# relay_bridge.net
KiCad netlist of a schematic drawn in Altium Designer
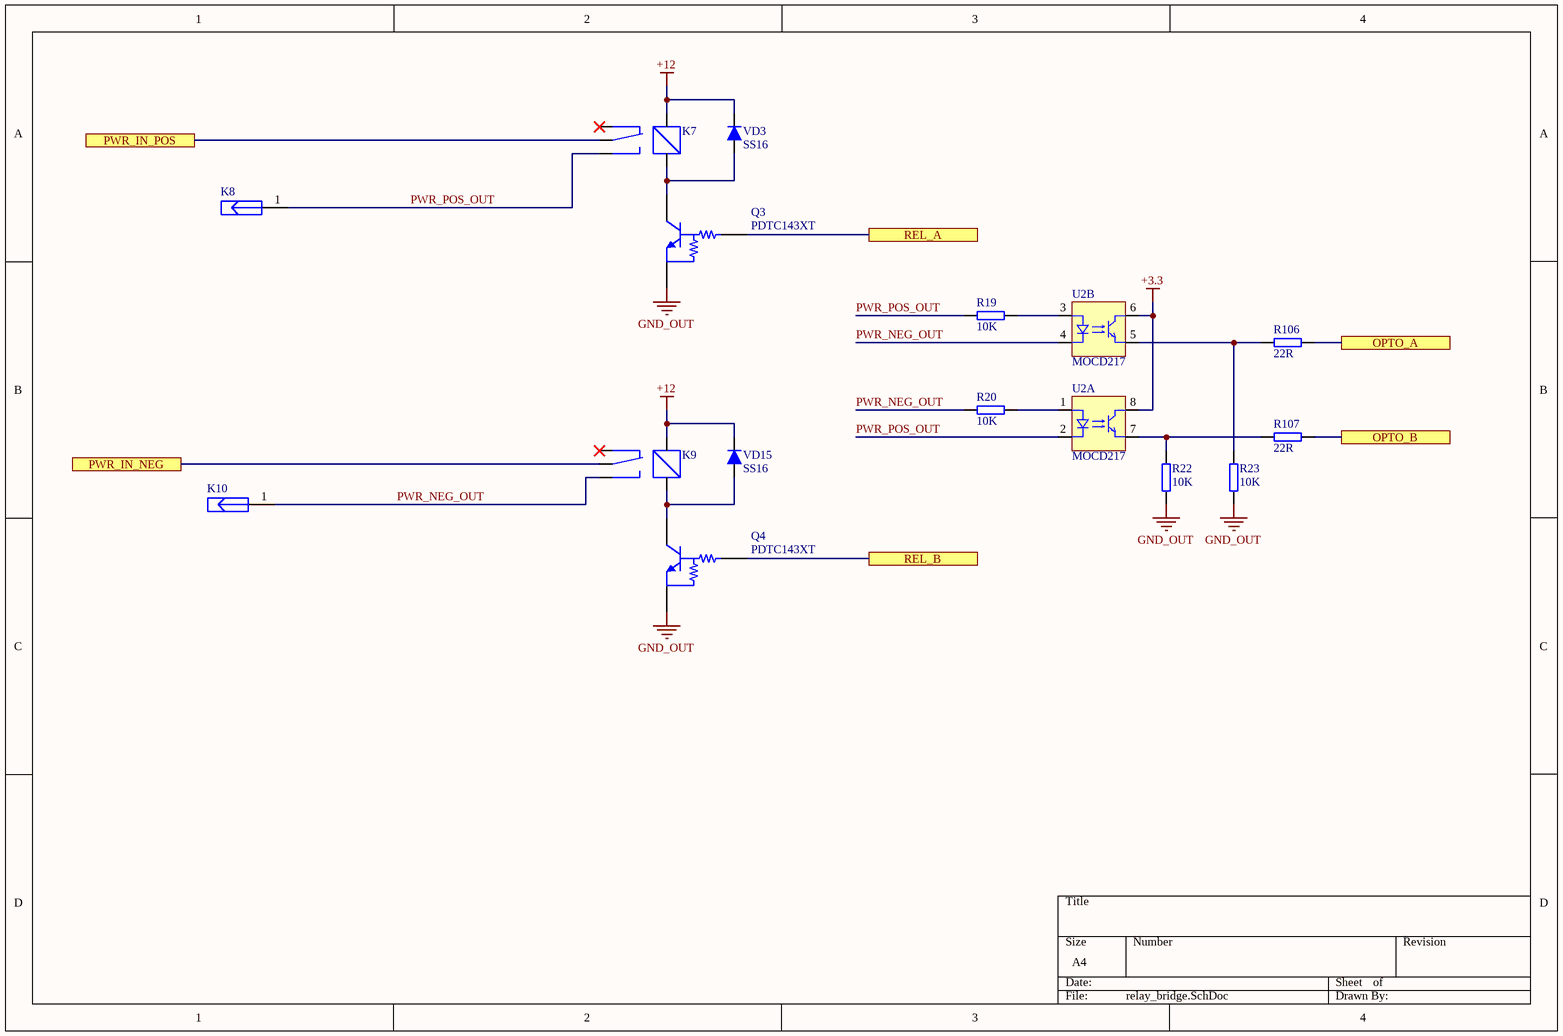
[diagram p0: relay_bridge.SchDoc]

(export (version "E")
  (design (tool "Eeschema 10.0.6"))
  (components
    (comp (ref "K7") (value "~") (footprint "REL: SRD-03VDC") (libsource (lib "OTHER") (part "Relay")))
    (comp (ref "K8") (value "~") (footprint "CON: 8191") (libsource (lib "OTHER") (part "PCB CON")))
    (comp (ref "K9") (value "~") (footprint "REL: SRD-03VDC") (libsource (lib "OTHER") (part "Relay")))
    (comp (ref "K10") (value "~") (footprint "CON: 8191") (libsource (lib "OTHER") (part "PCB CON")))
    (comp (ref "Q3")
      (value "PDTC143XT")
      (footprint "SOT23_N")
      (description "NPN Resistor-equipped Transistor")
      (fields (field (name "PUBLISHER") "Altium Limited"))
      (libsource (lib "Philips Discrete BJT - Low Power") (part "PDTC143XT"))
    )
    (comp (ref "Q4")
      (value "PDTC143XT")
      (footprint "SOT23_N")
      (description "NPN Resistor-equipped Transistor")
      (fields (field (name "PUBLISHER") "Altium Limited"))
      (libsource (lib "Philips Discrete BJT - Low Power") (part "PDTC143XT"))
    )
    (comp (ref "R19") (value "10K") (footprint "RES: 0603") (libsource (lib "PASSIVE") (part "R_SMD")))
    (comp (ref "R20") (value "10K") (footprint "RES: 0603") (libsource (lib "PASSIVE") (part "R_SMD")))
    (comp (ref "R22") (value "10K") (footprint "RES: 0603") (libsource (lib "PASSIVE") (part "R_SMD")))
    (comp (ref "R23") (value "10K") (footprint "RES: 0603") (libsource (lib "PASSIVE") (part "R_SMD")))
    (comp (ref "R106") (value "22R") (footprint "RES: 0603") (libsource (lib "PASSIVE") (part "R_SMD")))
    (comp (ref "R107") (value "22R") (footprint "RES: 0603") (libsource (lib "PASSIVE") (part "R_SMD")))
    (comp (ref "U2") (value "MOCD217") (footprint "8-SOIC") (libsource (lib "ANALOG") (part "MOCD217")))
    (comp (ref "VD3") (value "SS16") (footprint "DIODE: SMA") (libsource (lib "DIODES") (part "DIODE_SMD")))
    (comp (ref "VD15") (value "SS16") (footprint "DIODE: SMA") (libsource (lib "DIODES") (part "DIODE_SMD")))
  )
  (nets
    (net (code "1") (name "+3.3") (class "Default")
      (node (ref "U2") (pin "6") (pinfunction "C_6") (pintype "passive"))
      (node (ref "U2") (pin "8") (pinfunction "C_8") (pintype "passive"))
    )
    (net (code "2") (name "+12") (class "Default")
      (node (ref "K7") (pin "1") (pinfunction "a_1") (pintype "passive"))
      (node (ref "K9") (pin "1") (pinfunction "a_1") (pintype "passive"))
      (node (ref "VD15") (pin "2") (pinfunction "C_2") (pintype "passive"))
      (node (ref "VD3") (pin "2") (pinfunction "C_2") (pintype "passive"))
    )
    (net (code "3") (name "/OPTO_A") (class "Default")
      (node (ref "R106") (pin "1") (pinfunction "1_1") (pintype "passive"))
    )
    (net (code "4") (name "/OPTO_B") (class "Default")
      (node (ref "R107") (pin "1") (pinfunction "1_1") (pintype "passive"))
    )
    (net (code "5") (name "/PWR_IN_NEG") (class "Default")
      (node (ref "K9") (pin "3") (pinfunction "O_3") (pintype "passive"))
    )
    (net (code "6") (name "/PWR_IN_POS") (class "Default")
      (node (ref "K7") (pin "3") (pinfunction "O_3") (pintype "passive"))
    )
    (net (code "7") (name "/PWR_NEG_OUT") (class "Default")
      (node (ref "K10") (pin "1") (pintype "passive"))
      (node (ref "K9") (pin "5") (pinfunction "NO_5") (pintype "passive"))
      (node (ref "R20") (pin "2") (pinfunction "2_2") (pintype "passive"))
      (node (ref "U2") (pin "4") (pinfunction "K_4") (pintype "passive"))
    )
    (net (code "8") (name "/PWR_POS_OUT") (class "Default")
      (node (ref "K7") (pin "5") (pinfunction "NO_5") (pintype "passive"))
      (node (ref "K8") (pin "1") (pintype "passive"))
      (node (ref "R19") (pin "2") (pinfunction "2_2") (pintype "passive"))
      (node (ref "U2") (pin "2") (pinfunction "K_2") (pintype "passive"))
    )
    (net (code "9") (name "/REL_A") (class "Default")
      (node (ref "Q3") (pin "1") (pinfunction "B_1") (pintype "passive"))
    )
    (net (code "10") (name "/REL_B") (class "Default")
      (node (ref "Q4") (pin "1") (pinfunction "B_1") (pintype "passive"))
    )
    (net (code "11") (name "GND_OUT") (class "Default")
      (node (ref "Q3") (pin "2") (pinfunction "E_2") (pintype "passive"))
      (node (ref "Q4") (pin "2") (pinfunction "E_2") (pintype "passive"))
      (node (ref "R22") (pin "2") (pinfunction "2_2") (pintype "passive"))
      (node (ref "R23") (pin "2") (pinfunction "2_2") (pintype "passive"))
    )
    (net (code "12") (name "Net-(K7-b)") (class "Default")
      (node (ref "K7") (pin "2") (pinfunction "b_2") (pintype "passive"))
      (node (ref "Q3") (pin "3") (pinfunction "C_3") (pintype "passive"))
      (node (ref "VD3") (pin "1") (pinfunction "A_1") (pintype "passive"))
    )
    (net (code "13") (name "Net-(K9-b)") (class "Default")
      (node (ref "K9") (pin "2") (pinfunction "b_2") (pintype "passive"))
      (node (ref "Q4") (pin "3") (pinfunction "C_3") (pintype "passive"))
      (node (ref "VD15") (pin "1") (pinfunction "A_1") (pintype "passive"))
    )
    (net (code "14") (name "Net-(U2A-A)") (class "Default")
      (node (ref "R20") (pin "1") (pinfunction "1_1") (pintype "passive"))
      (node (ref "U2") (pin "1") (pinfunction "A_1") (pintype "passive"))
    )
    (net (code "15") (name "Net-(U2A-E)") (class "Default")
      (node (ref "R107") (pin "2") (pinfunction "2_2") (pintype "passive"))
      (node (ref "R22") (pin "1") (pinfunction "1_1") (pintype "passive"))
      (node (ref "U2") (pin "7") (pinfunction "E_7") (pintype "passive"))
    )
    (net (code "16") (name "Net-(U2B-A)") (class "Default")
      (node (ref "R19") (pin "1") (pinfunction "1_1") (pintype "passive"))
      (node (ref "U2") (pin "3") (pinfunction "A_3") (pintype "passive"))
    )
    (net (code "17") (name "Net-(U2B-E)") (class "Default")
      (node (ref "R106") (pin "2") (pinfunction "2_2") (pintype "passive"))
      (node (ref "R23") (pin "1") (pinfunction "1_1") (pintype "passive"))
      (node (ref "U2") (pin "5") (pinfunction "E_5") (pintype "passive"))
    )
    (net (code "18") (name "unconnected-(K7-NC-Pad4)") (class "Default")
      (node (ref "K7") (pin "4") (pinfunction "NC_4") (pintype "passive+no_connect"))
    )
    (net (code "19") (name "unconnected-(K9-NC-Pad4)") (class "Default")
      (node (ref "K9") (pin "4") (pinfunction "NC_4") (pintype "passive+no_connect"))
    )
  )
)
